# Schematic.net
KiCad netlist of a schematic drawn in Altium Designer
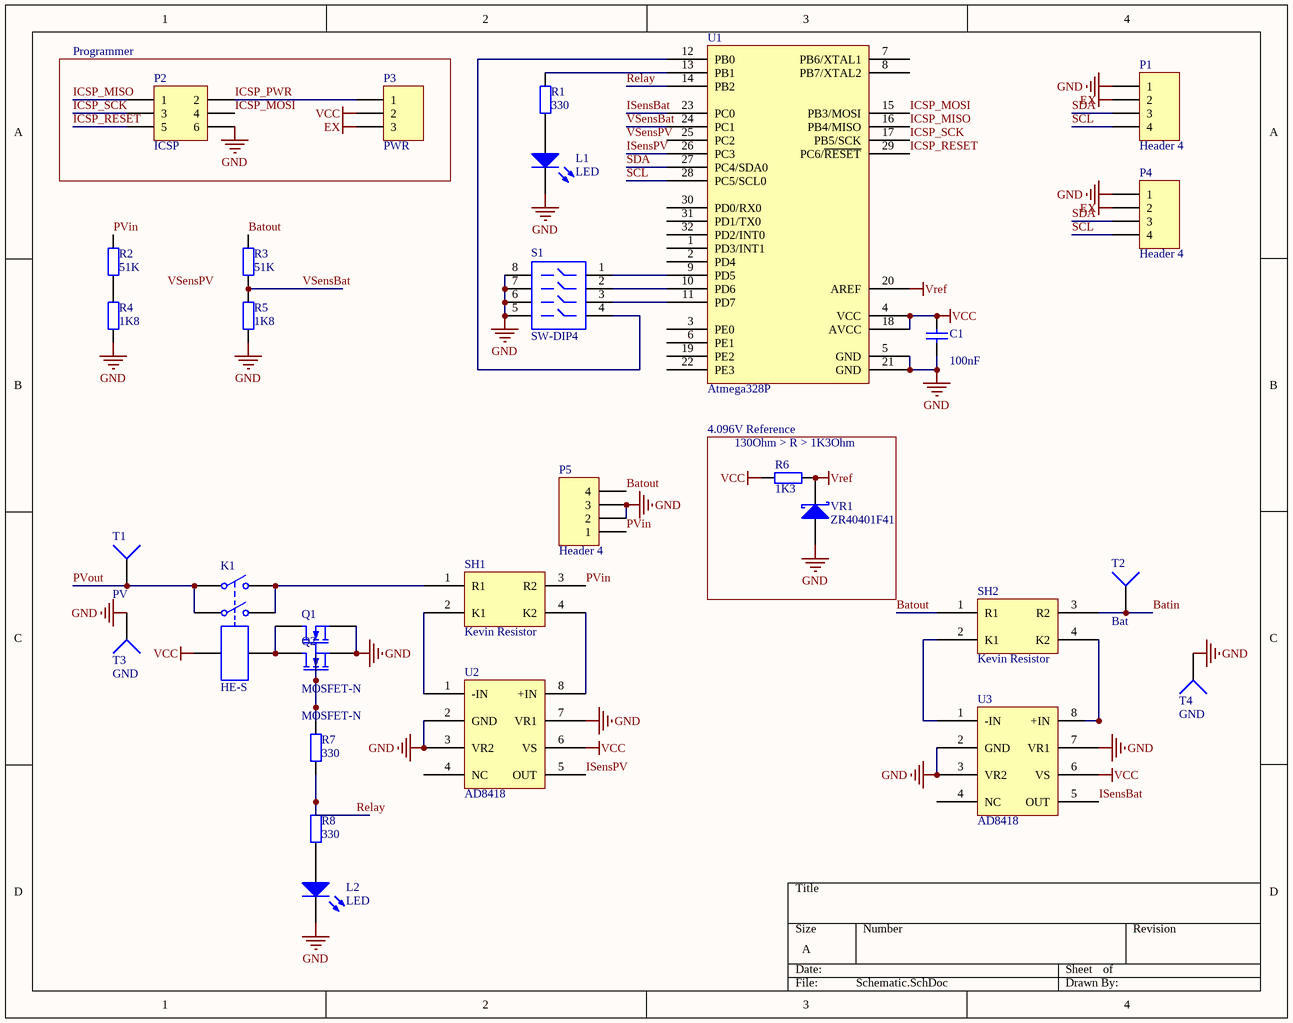
[diagram p0: Schematic.SchDoc]

(export (version "E")
  (design (tool "Eeschema 10.0.6"))
  (components
    (comp (ref "C1")
      (value "100nF")
      (footprint "CAP 0805/2012")
      (description "Capacitor")
      (fields (field (name "Comment") "Cap") (field (name "PUBLISHER") "Altium Limited"))
      (libsource (lib "Miscellaneous Devices") (part "Cap"))
    )
    (comp (ref "K1")
      (value "HE-S")
      (footprint "Relay HE-S Parasonic")
      (description "Dual-Pole Single-Throw Relay")
      (fields (field (name "PUBLISHER") "Altium Limited"))
      (libsource (lib "Miscellaneous Devices") (part "Relay-DPST"))
    )
    (comp (ref "L1")
      (value "LED")
      (footprint "LED 0805/2012 RED")
      (description "Typical INFRARED GaAs LED")
      (fields (field (name "PUBLISHER") "Altium Limited"))
      (libsource (lib "Miscellaneous Devices") (part "LED0"))
    )
    (comp (ref "L2")
      (value "LED")
      (footprint "LED 0805/2012 RED")
      (description "Typical INFRARED GaAs LED")
      (fields (field (name "PUBLISHER") "Altium Limited"))
      (libsource (lib "Miscellaneous Devices") (part "LED0"))
    )
    (comp (ref "P1")
      (value "Header 4")
      (footprint "TE 282834-4")
      (description "Header, 4-Pin")
      (fields (field (name "PUBLISHER") "Altium Limited"))
      (libsource (lib "Miscellaneous Connectors") (part "Header 4"))
    )
    (comp (ref "P2")
      (value "ICSP")
      (footprint "HDR2X3")
      (description "Header, 3-Pin, Dual row")
      (fields (field (name "PUBLISHER") "Altium Limited"))
      (libsource (lib "Miscellaneous Connectors") (part "Header 3X2"))
    )
    (comp (ref "P3")
      (value "PWR")
      (footprint "HDR1X3")
      (description "Header, 3-Pin")
      (fields (field (name "PUBLISHER") "Altium Limited"))
      (libsource (lib "Miscellaneous Connectors") (part "Header 3"))
    )
    (comp (ref "P4")
      (value "Header 4")
      (footprint "TE 282834-4")
      (description "Header, 4-Pin")
      (fields (field (name "PUBLISHER") "Altium Limited"))
      (libsource (lib "Miscellaneous Connectors") (part "Header 4"))
    )
    (comp (ref "P5")
      (value "Header 4")
      (footprint "4Pin 6.35mm Connector")
      (description "Header, 4-Pin")
      (fields (field (name "PUBLISHER") "Altium Limited"))
      (libsource (lib "") (part "Header 4_1"))
    )
    (comp (ref "Q1")
      (value "MOSFET-N")
      (footprint "SOT23_N")
      (description "N-Channel MOSFET")
      (fields (field (name "PUBLISHER") "Altium Limited"))
      (libsource (lib "Miscellaneous Devices") (part "MOSFET-N"))
    )
    (comp (ref "Q2")
      (value "MOSFET-N")
      (footprint "SOT23_N")
      (description "N-Channel MOSFET")
      (fields (field (name "PUBLISHER") "Altium Limited"))
      (libsource (lib "Miscellaneous Devices") (part "MOSFET-N"))
    )
    (comp (ref "R1")
      (value "330")
      (footprint "RES 0805/2012")
      (description "Resistor")
      (fields (field (name "Comment") "Res2") (field (name "PUBLISHER") "Altium Limited"))
      (libsource (lib "") (part "Res2_1"))
    )
    (comp (ref "R2")
      (value "51K")
      (footprint "RES 0805/2012")
      (description "Resistor")
      (fields (field (name "Comment") "Res2") (field (name "PUBLISHER") "Altium Limited"))
      (libsource (lib "") (part "Res2_1"))
    )
    (comp (ref "R3")
      (value "51K")
      (footprint "RES 0805/2012")
      (description "Resistor")
      (fields (field (name "Comment") "Res2") (field (name "PUBLISHER") "Altium Limited"))
      (libsource (lib "") (part "Res2_1"))
    )
    (comp (ref "R4")
      (value "1K8")
      (footprint "RES 0805/2012")
      (description "Resistor")
      (fields (field (name "Comment") "Res2") (field (name "PUBLISHER") "Altium Limited"))
      (libsource (lib "") (part "Res2_1"))
    )
    (comp (ref "R5")
      (value "1K8")
      (footprint "RES 0805/2012")
      (description "Resistor")
      (fields (field (name "Comment") "Res2") (field (name "PUBLISHER") "Altium Limited"))
      (libsource (lib "") (part "Res2_1"))
    )
    (comp (ref "R6")
      (value "1K3")
      (footprint "RES 0805/2012")
      (description "Resistor")
      (fields (field (name "Comment") "Res2") (field (name "PUBLISHER") "Altium Limited"))
      (libsource (lib "Miscellaneous Devices") (part "Res2"))
    )
    (comp (ref "R7")
      (value "330")
      (footprint "RES 0805/2012")
      (description "Resistor")
      (fields (field (name "Comment") "Res2") (field (name "PUBLISHER") "Altium Limited"))
      (libsource (lib "") (part "Res2_2"))
    )
    (comp (ref "R8")
      (value "330")
      (footprint "RES 0805/2012")
      (description "Resistor")
      (fields (field (name "Comment") "Res2") (field (name "PUBLISHER") "Altium Limited"))
      (libsource (lib "") (part "Res2_1"))
    )
    (comp (ref "S1")
      (value "SW-DIP4")
      (footprint "CTS 218-4LPJ")
      (description "DIP Switch")
      (fields (field (name "PUBLISHER") "Altium Limited"))
      (libsource (lib "Miscellaneous Devices") (part "SW-DIP4"))
    )
    (comp (ref "SH1")
      (value "Kevin Resistor")
      (footprint "TE TLR Shunt")
      (libsource (lib "Personal Library") (part "Kevin Resistor"))
    )
    (comp (ref "SH2")
      (value "Kevin Resistor")
      (footprint "TE TLR Shunt")
      (libsource (lib "Personal Library") (part "Kevin Resistor"))
    )
    (comp (ref "T1")
      (value "PV")
      (footprint "PCB_Pin_Outsteeksel")
      (description "Socket")
      (fields (field (name "PUBLISHER") "Altium Limited"))
      (libsource (lib "Miscellaneous Connectors") (part "Socket"))
    )
    (comp (ref "T2")
      (value "Bat")
      (footprint "PCB_Pin_Outsteeksel")
      (description "Socket")
      (fields (field (name "PUBLISHER") "Altium Limited"))
      (libsource (lib "Miscellaneous Connectors") (part "Socket"))
    )
    (comp (ref "T3")
      (value "GND")
      (footprint "PCB_Pin_Outsteeksel")
      (description "Socket")
      (fields (field (name "PUBLISHER") "Altium Limited"))
      (libsource (lib "Miscellaneous Connectors") (part "Socket"))
    )
    (comp (ref "T4")
      (value "GND")
      (footprint "PCB_Pin_Outsteeksel")
      (description "Socket")
      (fields (field (name "PUBLISHER") "Altium Limited"))
      (libsource (lib "Miscellaneous Connectors") (part "Socket"))
    )
    (comp (ref "U1")
      (value "Atmega328P")
      (footprint "ST LQFP-32 7X7MM")
      (libsource (lib "GJ24") (part "Atmega328P"))
    )
    (comp (ref "U2")
      (value "AD8418")
      (footprint "ANALOG MSOP-8 RM-8")
      (libsource (lib "GJ24") (part "AD8418"))
    )
    (comp (ref "U3")
      (value "AD8418")
      (footprint "ANALOG MSOP-8 RM-8")
      (libsource (lib "GJ24") (part "AD8418"))
    )
    (comp (ref "VR1")
      (value "ZR40401F41")
      (footprint "DIODES SOT-23-3")
      (description "Schottky Rectifier")
      (fields (field (name "PUBLISHER") "Altium Limited"))
      (libsource (lib "Miscellaneous Devices") (part "Diode 10TQ035"))
    )
  )
  (nets
    (net (code "1") (name "/Batin") (class "Default")
      (node (ref "SH2") (pin "3") (pinfunction "R2_3") (pintype "passive"))
      (node (ref "T2") (pin "1") (pinfunction "1_1") (pintype "passive"))
    )
    (net (code "2") (name "/Batout") (class "Default")
      (node (ref "P5") (pin "4") (pinfunction "4_4") (pintype "passive"))
      (node (ref "R3") (pin "2") (pinfunction "2_2") (pintype "passive"))
      (node (ref "SH2") (pin "1") (pinfunction "R1_1") (pintype "passive"))
    )
    (net (code "3") (name "/ICSP_MISO") (class "Default")
      (node (ref "P2") (pin "1") (pinfunction "1_1") (pintype "passive"))
      (node (ref "U1") (pin "16") (pinfunction "PB4/MISO_16") (pintype "passive"))
    )
    (net (code "4") (name "/ICSP_MOSI") (class "Default")
      (node (ref "P2") (pin "4") (pinfunction "4_4") (pintype "passive"))
      (node (ref "U1") (pin "15") (pinfunction "PB3/MOSI_15") (pintype "passive"))
    )
    (net (code "5") (name "/ICSP_PWR") (class "Default")
      (node (ref "P2") (pin "2") (pinfunction "2_2") (pintype "passive"))
      (node (ref "P3") (pin "1") (pinfunction "1_1") (pintype "passive"))
    )
    (net (code "6") (name "/ICSP_RESET") (class "Default")
      (node (ref "P2") (pin "5") (pinfunction "5_5") (pintype "passive"))
      (node (ref "U1") (pin "29") (pinfunction "PC6/~{RESET}_29") (pintype "passive"))
    )
    (net (code "7") (name "/ICSP_SCK") (class "Default")
      (node (ref "P2") (pin "3") (pinfunction "3_3") (pintype "passive"))
      (node (ref "U1") (pin "17") (pinfunction "PB5/SCK_17") (pintype "passive"))
    )
    (net (code "8") (name "/ISensBat") (class "Default")
      (node (ref "U1") (pin "23") (pinfunction "PC0_23") (pintype "passive"))
      (node (ref "U3") (pin "5") (pinfunction "OUT_5") (pintype "passive"))
    )
    (net (code "9") (name "/ISensPV") (class "Default")
      (node (ref "U1") (pin "26") (pinfunction "PC3_26") (pintype "passive"))
      (node (ref "U2") (pin "5") (pinfunction "OUT_5") (pintype "passive"))
    )
    (net (code "10") (name "/PVin") (class "Default")
      (node (ref "P5") (pin "1") (pinfunction "1_1") (pintype "passive"))
      (node (ref "R2") (pin "2") (pinfunction "2_2") (pintype "passive"))
      (node (ref "SH1") (pin "3") (pinfunction "R2_3") (pintype "passive"))
    )
    (net (code "11") (name "/PVout") (class "Default")
      (node (ref "K1") (pin "1") (pinfunction "1_1") (pintype "passive"))
      (node (ref "K1") (pin "3") (pinfunction "3_3") (pintype "passive"))
      (node (ref "T1") (pin "1") (pinfunction "1_1") (pintype "passive"))
    )
    (net (code "12") (name "/Relay") (class "Default")
      (node (ref "R7") (pin "2") (pinfunction "2_2") (pintype "passive"))
      (node (ref "R8") (pin "2") (pinfunction "2_2") (pintype "passive"))
      (node (ref "U1") (pin "14") (pinfunction "PB2_14") (pintype "passive"))
    )
    (net (code "13") (name "/SCL") (class "Default")
      (node (ref "P1") (pin "4") (pinfunction "4_4") (pintype "passive"))
      (node (ref "P4") (pin "4") (pinfunction "4_4") (pintype "passive"))
      (node (ref "U1") (pin "28") (pinfunction "PC5/SCL0_28") (pintype "passive"))
    )
    (net (code "14") (name "/SDA") (class "Default")
      (node (ref "P1") (pin "3") (pinfunction "3_3") (pintype "passive"))
      (node (ref "P4") (pin "3") (pinfunction "3_3") (pintype "passive"))
      (node (ref "U1") (pin "27") (pinfunction "PC4/SDA0_27") (pintype "passive"))
    )
    (net (code "15") (name "/VSensBat") (class "Default")
      (node (ref "R3") (pin "1") (pinfunction "1_1") (pintype "passive"))
      (node (ref "R5") (pin "2") (pinfunction "2_2") (pintype "passive"))
      (node (ref "U1") (pin "24") (pinfunction "PC1_24") (pintype "passive"))
    )
    (net (code "17") (name "EX") (class "Default")
      (node (ref "P1") (pin "2") (pinfunction "2_2") (pintype "passive"))
      (node (ref "P3") (pin "3") (pinfunction "3_3") (pintype "passive"))
      (node (ref "P4") (pin "2") (pinfunction "2_2") (pintype "passive"))
    )
    (net (code "18") (name "GND") (class "Default")
      (node (ref "C1") (pin "1") (pinfunction "1_1") (pintype "passive"))
      (node (ref "L1") (pin "2") (pinfunction "K_2") (pintype "passive"))
      (node (ref "L2") (pin "2") (pinfunction "K_2") (pintype "passive"))
      (node (ref "P1") (pin "1") (pinfunction "1_1") (pintype "passive"))
      (node (ref "P2") (pin "6") (pinfunction "6_6") (pintype "passive"))
      (node (ref "P4") (pin "1") (pinfunction "1_1") (pintype "passive"))
      (node (ref "P5") (pin "2") (pinfunction "2_2") (pintype "passive"))
      (node (ref "P5") (pin "3") (pinfunction "3_3") (pintype "passive"))
      (node (ref "Q1") (pin "2") (pinfunction "S_2") (pintype "passive"))
      (node (ref "Q2") (pin "2") (pinfunction "S_2") (pintype "passive"))
      (node (ref "R4") (pin "1") (pinfunction "1_1") (pintype "passive"))
      (node (ref "R5") (pin "1") (pinfunction "1_1") (pintype "passive"))
      (node (ref "S1") (pin "5") (pinfunction "5_5") (pintype "passive"))
      (node (ref "S1") (pin "6") (pinfunction "6_6") (pintype "passive"))
      (node (ref "S1") (pin "7") (pinfunction "7_7") (pintype "passive"))
      (node (ref "S1") (pin "8") (pinfunction "8_8") (pintype "passive"))
      (node (ref "T3") (pin "1") (pinfunction "1_1") (pintype "passive"))
      (node (ref "T4") (pin "1") (pinfunction "1_1") (pintype "passive"))
      (node (ref "U1") (pin "21") (pinfunction "GND_21") (pintype "passive"))
      (node (ref "U1") (pin "5") (pinfunction "GND_5") (pintype "passive"))
      (node (ref "U2") (pin "2") (pinfunction "GND_2") (pintype "passive"))
      (node (ref "U2") (pin "3") (pinfunction "VR2_3") (pintype "passive"))
      (node (ref "U2") (pin "7") (pinfunction "VR1_7") (pintype "passive"))
      (node (ref "U3") (pin "2") (pinfunction "GND_2") (pintype "passive"))
      (node (ref "U3") (pin "3") (pinfunction "VR2_3") (pintype "passive"))
      (node (ref "U3") (pin "7") (pinfunction "VR1_7") (pintype "passive"))
      (node (ref "VR1") (pin "3") (pinfunction "A_3") (pintype "passive"))
    )
    (net (code "19") (name "Net-(L1-A)") (class "Default")
      (node (ref "L1") (pin "1") (pinfunction "A_1") (pintype "passive"))
      (node (ref "R1") (pin "1") (pinfunction "1_1") (pintype "passive"))
    )
    (net (code "20") (name "Net-(L2-A)") (class "Default")
      (node (ref "L2") (pin "1") (pinfunction "A_1") (pintype "passive"))
      (node (ref "R8") (pin "1") (pinfunction "1_1") (pintype "passive"))
    )
    (net (code "21") (name "Net-(Q1-D)") (class "Default")
      (node (ref "K1") (pin "6") (pinfunction "6_6") (pintype "passive"))
      (node (ref "Q1") (pin "1") (pinfunction "D_1") (pintype "passive"))
      (node (ref "Q2") (pin "1") (pinfunction "D_1") (pintype "passive"))
    )
    (net (code "22") (name "Net-(Q1-G)") (class "Default")
      (node (ref "Q1") (pin "3") (pinfunction "G_3") (pintype "passive"))
      (node (ref "Q2") (pin "3") (pinfunction "G_3") (pintype "passive"))
      (node (ref "R7") (pin "1") (pinfunction "1_1") (pintype "passive"))
    )
    (net (code "23") (name "Net-(R2-Pad1)") (class "Default")
      (node (ref "R2") (pin "1") (pinfunction "1_1") (pintype "passive"))
      (node (ref "R4") (pin "2") (pinfunction "2_2") (pintype "passive"))
    )
    (net (code "24") (name "Net-(SH1-K1)") (class "Default")
      (node (ref "SH1") (pin "2") (pinfunction "K1_2") (pintype "passive"))
      (node (ref "U2") (pin "1") (pinfunction "-IN_1") (pintype "passive"))
    )
    (net (code "25") (name "Net-(SH1-K2)") (class "Default")
      (node (ref "SH1") (pin "4") (pinfunction "K2_4") (pintype "passive"))
      (node (ref "U2") (pin "8") (pinfunction "+IN_8") (pintype "passive"))
    )
    (net (code "26") (name "Net-(SH1-R1)") (class "Default")
      (node (ref "K1") (pin "2") (pinfunction "2_2") (pintype "passive"))
      (node (ref "K1") (pin "4") (pinfunction "4_4") (pintype "passive"))
      (node (ref "SH1") (pin "1") (pinfunction "R1_1") (pintype "passive"))
    )
    (net (code "27") (name "Net-(SH2-K1)") (class "Default")
      (node (ref "SH2") (pin "2") (pinfunction "K1_2") (pintype "passive"))
      (node (ref "U3") (pin "1") (pinfunction "-IN_1") (pintype "passive"))
    )
    (net (code "28") (name "Net-(SH2-K2)") (class "Default")
      (node (ref "SH2") (pin "4") (pinfunction "K2_4") (pintype "passive"))
      (node (ref "U3") (pin "8") (pinfunction "+IN_8") (pintype "passive"))
    )
    (net (code "29") (name "Net-(U1-PB0)") (class "Default")
      (node (ref "S1") (pin "4") (pinfunction "4_4") (pintype "passive"))
      (node (ref "U1") (pin "12") (pinfunction "PB0_12") (pintype "passive"))
    )
    (net (code "30") (name "Net-(U1-PB1)") (class "Default")
      (node (ref "R1") (pin "2") (pinfunction "2_2") (pintype "passive"))
      (node (ref "U1") (pin "13") (pinfunction "PB1_13") (pintype "passive"))
    )
    (net (code "31") (name "Net-(U1-PD5)") (class "Default")
      (node (ref "S1") (pin "1") (pinfunction "1_1") (pintype "passive"))
      (node (ref "U1") (pin "9") (pinfunction "PD5_9") (pintype "passive"))
    )
    (net (code "32") (name "Net-(U1-PD6)") (class "Default")
      (node (ref "S1") (pin "2") (pinfunction "2_2") (pintype "passive"))
      (node (ref "U1") (pin "10") (pinfunction "PD6_10") (pintype "passive"))
    )
    (net (code "33") (name "Net-(U1-PD7)") (class "Default")
      (node (ref "S1") (pin "3") (pinfunction "3_3") (pintype "passive"))
      (node (ref "U1") (pin "11") (pinfunction "PD7_11") (pintype "passive"))
    )
    (net (code "34") (name "VCC") (class "Default")
      (node (ref "C1") (pin "2") (pinfunction "2_2") (pintype "passive"))
      (node (ref "K1") (pin "5") (pinfunction "5_5") (pintype "passive"))
      (node (ref "P3") (pin "2") (pinfunction "2_2") (pintype "passive"))
      (node (ref "R6") (pin "2") (pinfunction "2_2") (pintype "passive"))
      (node (ref "U1") (pin "18") (pinfunction "AVCC_18") (pintype "passive"))
      (node (ref "U1") (pin "4") (pinfunction "VCC_4") (pintype "passive"))
      (node (ref "U2") (pin "6") (pinfunction "VS_6") (pintype "passive"))
      (node (ref "U3") (pin "6") (pinfunction "VS_6") (pintype "passive"))
    )
    (net (code "35") (name "Vref") (class "Default")
      (node (ref "R6") (pin "1") (pinfunction "1_1") (pintype "passive"))
      (node (ref "U1") (pin "20") (pinfunction "AREF_20") (pintype "passive"))
      (node (ref "VR1") (pin "1") (pinfunction "K_1") (pintype "passive"))
    )
    (net (code "36") (name "unconnected-(U1-PB6{slash}XTAL1-Pad7)") (class "Default")
      (node (ref "U1") (pin "7") (pinfunction "PB6/XTAL1_7") (pintype "passive"))
    )
    (net (code "37") (name "unconnected-(U1-PB7{slash}XTAL2-Pad8)") (class "Default")
      (node (ref "U1") (pin "8") (pinfunction "PB7/XTAL2_8") (pintype "passive"))
    )
    (net (code "38") (name "unconnected-(U1-PC2-Pad25)") (class "Default")
      (node (ref "U1") (pin "25") (pinfunction "PC2_25") (pintype "passive"))
    )
    (net (code "39") (name "unconnected-(U1-PD0{slash}RX0-Pad30)") (class "Default")
      (node (ref "U1") (pin "30") (pinfunction "PD0/RX0_30") (pintype "passive"))
    )
    (net (code "40") (name "unconnected-(U1-PD1{slash}TX0-Pad31)") (class "Default")
      (node (ref "U1") (pin "31") (pinfunction "PD1/TX0_31") (pintype "passive"))
    )
    (net (code "41") (name "unconnected-(U1-PD2{slash}INT0-Pad32)") (class "Default")
      (node (ref "U1") (pin "32") (pinfunction "PD2/INT0_32") (pintype "passive"))
    )
    (net (code "42") (name "unconnected-(U1-PD3{slash}INT1-Pad1)") (class "Default")
      (node (ref "U1") (pin "1") (pinfunction "PD3/INT1_1") (pintype "passive"))
    )
    (net (code "43") (name "unconnected-(U1-PD4-Pad2)") (class "Default")
      (node (ref "U1") (pin "2") (pinfunction "PD4_2") (pintype "passive"))
    )
    (net (code "44") (name "unconnected-(U1-PE0-Pad3)") (class "Default")
      (node (ref "U1") (pin "3") (pinfunction "PE0_3") (pintype "passive"))
    )
    (net (code "45") (name "unconnected-(U1-PE1-Pad6)") (class "Default")
      (node (ref "U1") (pin "6") (pinfunction "PE1_6") (pintype "passive"))
    )
    (net (code "46") (name "unconnected-(U1-PE2-Pad19)") (class "Default")
      (node (ref "U1") (pin "19") (pinfunction "PE2_19") (pintype "passive"))
    )
    (net (code "47") (name "unconnected-(U1-PE3-Pad22)") (class "Default")
      (node (ref "U1") (pin "22") (pinfunction "PE3_22") (pintype "passive"))
    )
    (net (code "48") (name "unconnected-(U2-NC-Pad4)") (class "Default")
      (node (ref "U2") (pin "4") (pinfunction "NC_4") (pintype "passive"))
    )
    (net (code "49") (name "unconnected-(U3-NC-Pad4)") (class "Default")
      (node (ref "U3") (pin "4") (pinfunction "NC_4") (pintype "passive"))
    )
  )
)
